# CMWX_LoRa_GPS_v14_Test.net
KiCad netlist of a schematic drawn in EAGLE
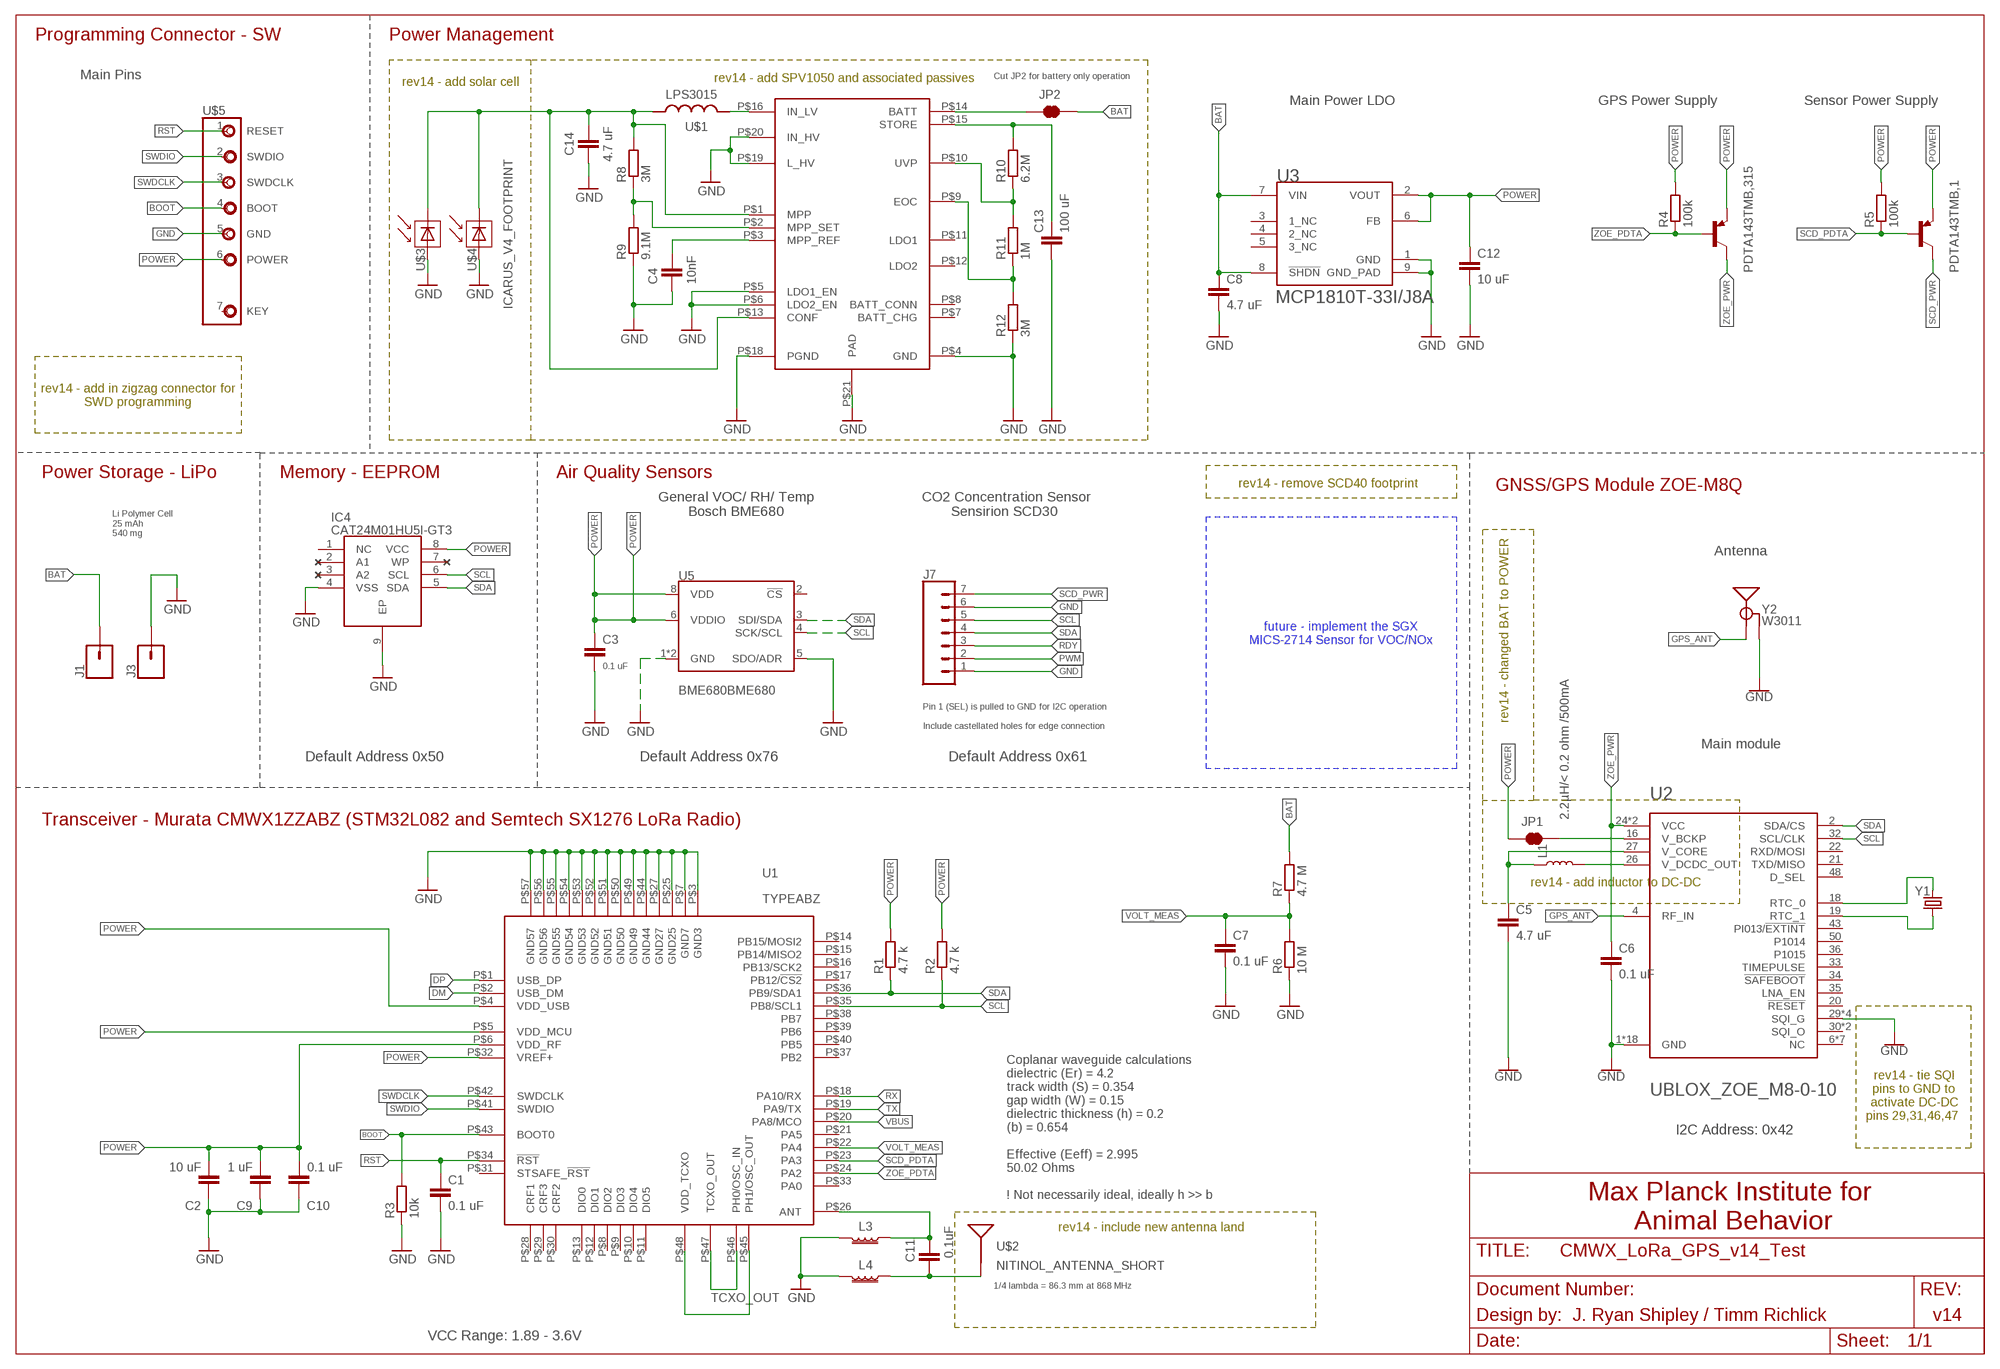
[diagram p0: schematic, sheet 1]

(export (version "E")
  (design (tool "Eeschema 10.0.6"))
  (components
    (comp (ref "C1")
      (value "0.1 uF")
      (footprint "eagle-import:C0201")
      (libsource (lib "eagle-import") (part "C-EUC0201"))
    )
    (comp (ref "C2")
      (value "10 uF")
      (footprint "eagle-import:C0201")
      (libsource (lib "eagle-import") (part "C-EUC0201"))
    )
    (comp (ref "C3")
      (value "0.1 uF")
      (footprint "eagle-import:C0201")
      (libsource (lib "eagle-import") (part "C-EUC0201"))
    )
    (comp (ref "C4")
      (value "10nF")
      (footprint "eagle-import:C0201")
      (libsource (lib "eagle-import") (part "C-EUC0201"))
    )
    (comp (ref "C5")
      (value "4.7 uF")
      (footprint "eagle-import:C0201")
      (libsource (lib "eagle-import") (part "C-EUC0201"))
    )
    (comp (ref "C6")
      (value "0.1 uF")
      (footprint "eagle-import:C0201")
      (libsource (lib "eagle-import") (part "C-EUC0201"))
    )
    (comp (ref "C7")
      (value "0.1 uF")
      (footprint "eagle-import:C0201")
      (libsource (lib "eagle-import") (part "C-EUC0201"))
    )
    (comp (ref "C8")
      (value "4.7 uF")
      (footprint "eagle-import:C0201")
      (libsource (lib "eagle-import") (part "C-EUC0201"))
    )
    (comp (ref "C9")
      (value "1 uF")
      (footprint "eagle-import:C0201")
      (libsource (lib "eagle-import") (part "C-EUC0201"))
    )
    (comp (ref "C10")
      (value "0.1 uF")
      (footprint "eagle-import:C0201")
      (libsource (lib "eagle-import") (part "C-EUC0201"))
    )
    (comp (ref "C11")
      (value "0.1uF")
      (footprint "eagle-import:0402-TIGHT")
      (libsource (lib "eagle-import") (part "0.1UF-0402T-16V-10%"))
    )
    (comp (ref "C12")
      (value "10 uF")
      (footprint "eagle-import:C0201")
      (libsource (lib "eagle-import") (part "C-EUC0201"))
    )
    (comp (ref "C13")
      (value "100 uF")
      (footprint "eagle-import:C0201")
      (libsource (lib "eagle-import") (part "C-EUC0201"))
    )
    (comp (ref "C14")
      (value "4.7 uF")
      (footprint "eagle-import:C0201")
      (libsource (lib "eagle-import") (part "C-EUC0201"))
    )
    (comp (ref "IC4")
      (value "CAT24M01HU5I-GT3")
      (footprint "eagle-import:SON50P300X200X55-9N")
      (fields
        (field (name "MOUSER_PART_NUMBER") "863-CAT24M01HU5I-GT3")
        (field (name "RS_PART_NUMBER") "7814831P")
      )
      (libsource (lib "eagle-import") (part "CAT24M01HU5I-GT3"))
    )
    (comp (ref "J1")
      (value "CONN_01PTH_NO_SILK_YES_STOP")
      (footprint "eagle-import:1X01_NO_SILK")
      (libsource (lib "eagle-import") (part "CONN_01PTH_NO_SILK_YES_STOP"))
    )
    (comp (ref "J3")
      (value "CONN_01PTH_NO_SILK_YES_STOP")
      (footprint "eagle-import:1X01_NO_SILK")
      (libsource (lib "eagle-import") (part "CONN_01PTH_NO_SILK_YES_STOP"))
    )
    (comp (ref "J7")
      (value "CONN_07NO_SILK")
      (footprint "eagle-import:1X07_NO_SILK")
      (libsource (lib "eagle-import") (part "CONN_07NO_SILK"))
    )
    (comp (ref "JP1")
      (value "JUMPER-SMT_2_NC_TRACE_NO-SILK")
      (footprint "eagle-import:SMT-JUMPER_2_NC_TRACE_NO-SILK")
      (libsource (lib "eagle-import") (part "JUMPER-SMT_2_NC_TRACE_NO-SILK"))
    )
    (comp (ref "JP2")
      (value "JUMPER-SMT_2_NC_TRACE_NO-SILK")
      (footprint "eagle-import:SMT-JUMPER_2_NC_TRACE_NO-SILK")
      (libsource (lib "eagle-import") (part "JUMPER-SMT_2_NC_TRACE_NO-SILK"))
    )
    (comp (ref "L1")
      (value "2.2µH/< 0.2 ohm /500mA")
      (footprint "eagle-import:0805")
      (libsource (lib "eagle-import") (part "INDUCTOR-0805-3.3UH"))
    )
    (comp (ref "L3")
      (value "FERRITE_BEAD-120_OHM_TIGHT")
      (footprint "eagle-import:0402-TIGHT")
      (libsource (lib "eagle-import") (part "FERRITE_BEAD-120_OHM_TIGHT"))
    )
    (comp (ref "L4")
      (value "FERRITE_BEAD-120_OHM_TIGHT")
      (footprint "eagle-import:0402-TIGHT")
      (libsource (lib "eagle-import") (part "FERRITE_BEAD-120_OHM_TIGHT"))
    )
    (comp (ref "PDTA143TMB,1")
      (value "TINYPICO-PNPAMB")
      (footprint "eagle-import:SOT883(B)")
      (libsource (lib "eagle-import") (part "TINYPICO-PNPMBA"))
    )
    (comp (ref "PDTA143TMB,315")
      (value "TINYPICO-PNPAMB")
      (footprint "eagle-import:SOT883(B)")
      (libsource (lib "eagle-import") (part "TINYPICO-PNPMBA"))
    )
    (comp (ref "R1")
      (value "4.7 k")
      (footprint "eagle-import:R0201")
      (libsource (lib "eagle-import") (part "R-EU_R0201"))
    )
    (comp (ref "R2")
      (value "4.7 k")
      (footprint "eagle-import:R0201")
      (libsource (lib "eagle-import") (part "R-EU_R0201"))
    )
    (comp (ref "R3")
      (value "10k")
      (footprint "eagle-import:R0201")
      (libsource (lib "eagle-import") (part "R-EU_R0201"))
    )
    (comp (ref "R4")
      (value "100k")
      (footprint "eagle-import:R0201")
      (libsource (lib "eagle-import") (part "R-EU_R0201"))
    )
    (comp (ref "R5")
      (value "100k")
      (footprint "eagle-import:R0201")
      (libsource (lib "eagle-import") (part "R-EU_R0201"))
    )
    (comp (ref "R6")
      (value "10 M")
      (footprint "eagle-import:R0201")
      (libsource (lib "eagle-import") (part "R-EU_R0201"))
    )
    (comp (ref "R7")
      (value "4.7 M")
      (footprint "eagle-import:R0201")
      (libsource (lib "eagle-import") (part "R-EU_R0201"))
    )
    (comp (ref "R8")
      (value "3M")
      (footprint "eagle-import:R0201")
      (libsource (lib "eagle-import") (part "R-EU_R0201"))
    )
    (comp (ref "R9")
      (value "9.1M")
      (footprint "eagle-import:R0201")
      (libsource (lib "eagle-import") (part "R-EU_R0201"))
    )
    (comp (ref "R10")
      (value "6.2M")
      (footprint "eagle-import:R0201")
      (libsource (lib "eagle-import") (part "R-EU_R0201"))
    )
    (comp (ref "R11")
      (value "1M")
      (footprint "eagle-import:R0201")
      (libsource (lib "eagle-import") (part "R-EU_R0201"))
    )
    (comp (ref "R12")
      (value "3M")
      (footprint "eagle-import:R0201")
      (libsource (lib "eagle-import") (part "R-EU_R0201"))
    )
    (comp (ref "U$1")
      (value "LPS3015")
      (footprint "eagle-import:LPS_3015")
      (libsource (lib "eagle-import") (part "LPS3015"))
    )
    (comp (ref "U$2")
      (value "NITINOL_ANTENNA_SHORT")
      (footprint "eagle-import:ICARUS_NITINOL_ANTENNA_SHORT")
      (libsource (lib "eagle-import") (part "NITINOL_ANTENNA_SHORT"))
    )
    (comp (ref "U$3")
      (value "ICARUS_V4_FOOTPRINT")
      (footprint "eagle-import:ICARUS_FULL_FOOTPRINT")
      (libsource (lib "eagle-import") (part "ICARUS_V4_FOOTPRINT"))
    )
    (comp (ref "U$4")
      (value "ICARUS_V4_FOOTPRINT")
      (footprint "eagle-import:ICARUS_FULL_FOOTPRINT")
      (libsource (lib "eagle-import") (part "ICARUS_V4_FOOTPRINT"))
    )
    (comp (ref "U$5")
      (value "ALBERT_ZIGZAG-ISP")
      (footprint "eagle-import:ALBERT_ZIGZAG-ISP")
      (libsource (lib "eagle-import") (part "ALBERT_ZIGZAG-ISP"))
    )
    (comp (ref "U1")
      (value "TYPEABZ")
      (footprint "eagle-import:TYPEABZ")
      (libsource (lib "eagle-import") (part "TYPEABZ"))
    )
    (comp (ref "U2")
      (value "UBLOX_ZOE_M8-0-10")
      (footprint "eagle-import:UBLOX_ZOE_M8-0-10")
      (libsource (lib "eagle-import") (part "UBLOX_ZOE_M8-0-10"))
    )
    (comp (ref "U3")
      (value "MICROCHIP_MCP1810T-33I-J8AMICROCHIP_MCP1810T-33I-J8A_0_0")
      (footprint "eagle-import:MICROCHIP_MCP1810T-33I-J8A_0")
      (fields
        (field (name "DIGIKEY_PART_NUMBER") "MCP1810T-33I/J8ACT-ND")
        (field (name "MF") "Microchip")
        (field (name "MOUSER_PART_NUMBER") "579-MCP1810T-33I/J8A")
      )
      (libsource (lib "eagle-import") (part "MICROCHIP_MCP1810T-33I-J8AMICROCHIP_MCP1810T-33I-J8A_0_0"))
    )
    (comp (ref "U4")
      (value "SPV1050")
      (footprint "eagle-import:SPV1050")
      (libsource (lib "eagle-import") (part "SPV1050"))
    )
    (comp (ref "U5")
      (value "BME680BME680")
      (footprint "eagle-import:LGA3.0X3.0")
      (libsource (lib "eagle-import") (part "BME680BME680"))
    )
    (comp (ref "Y1")
      (value "32.768kHz")
      (footprint "eagle-import:CRYSTAL-SMD-1.0X1.2MM")
      (libsource (lib "eagle-import") (part "CRYSTAL-32.768KHZ"))
    )
    (comp (ref "Y2")
      (value "W3011")
      (footprint "eagle-import:W3011")
      (libsource (lib "eagle-import") (part "GPS_CHIP_ANTENNAW3011"))
    )
  )
  (nets
    (net (code "1") (name "/TCXO_OUT") (class "Default")
      (node (ref "U1") (pin "P$46") (pinfunction "PH0/OSC_IN_P$46") (pintype "bidirectional"))
      (node (ref "U1") (pin "P$47") (pinfunction "TCXO_OUT_P$47") (pintype "bidirectional"))
    )
    (net (code "2") (name "BAT") (class "Default")
      (node (ref "C8") (pin "1") (pinfunction "1_1") (pintype "passive"))
      (node (ref "J1") (pin "1") (pinfunction "1_1") (pintype "passive"))
      (node (ref "JP2") (pin "2") (pinfunction "2_2") (pintype "passive"))
      (node (ref "R7") (pin "2") (pinfunction "2_2") (pintype "passive"))
      (node (ref "U3") (pin "7") (pinfunction "VIN_7") (pintype "bidirectional"))
      (node (ref "U3") (pin "8") (pinfunction "~{SHDN}_8") (pintype "bidirectional"))
    )
    (net (code "3") (name "BOOT") (class "Default")
      (node (ref "R3") (pin "2") (pinfunction "2_2") (pintype "passive"))
      (node (ref "U$5") (pin "4") (pinfunction "BOOT_4") (pintype "passive"))
      (node (ref "U1") (pin "P$43") (pinfunction "BOOT0_P$43") (pintype "bidirectional"))
    )
    (net (code "4") (name "DM") (class "Default")
      (node (ref "U1") (pin "P$2") (pinfunction "USB_DM_P$2") (pintype "bidirectional"))
    )
    (net (code "5") (name "DP") (class "Default")
      (node (ref "U1") (pin "P$1") (pinfunction "USB_DP_P$1") (pintype "bidirectional"))
    )
    (net (code "6") (name "GND") (class "Default")
      (node (ref "C1") (pin "2") (pinfunction "2_2") (pintype "passive"))
      (node (ref "C10") (pin "1") (pinfunction "1_1") (pintype "passive"))
      (node (ref "C12") (pin "2") (pinfunction "2_2") (pintype "passive"))
      (node (ref "C13") (pin "2") (pinfunction "2_2") (pintype "passive"))
      (node (ref "C14") (pin "2") (pinfunction "2_2") (pintype "passive"))
      (node (ref "C2") (pin "1") (pinfunction "1_1") (pintype "passive"))
      (node (ref "C3") (pin "2") (pinfunction "2_2") (pintype "passive"))
      (node (ref "C4") (pin "2") (pinfunction "2_2") (pintype "passive"))
      (node (ref "C5") (pin "2") (pinfunction "2_2") (pintype "passive"))
      (node (ref "C6") (pin "2") (pinfunction "2_2") (pintype "passive"))
      (node (ref "C7") (pin "2") (pinfunction "2_2") (pintype "passive"))
      (node (ref "C8") (pin "2") (pinfunction "2_2") (pintype "passive"))
      (node (ref "C9") (pin "1") (pinfunction "1_1") (pintype "passive"))
      (node (ref "IC4") (pin "4") (pinfunction "VSS_4") (pintype "power_in"))
      (node (ref "IC4") (pin "9") (pinfunction "EP_9") (pintype "bidirectional"))
      (node (ref "J3") (pin "1") (pinfunction "1_1") (pintype "passive"))
      (node (ref "J7") (pin "1") (pinfunction "1_1") (pintype "passive"))
      (node (ref "J7") (pin "6") (pinfunction "6_6") (pintype "passive"))
      (node (ref "L3") (pin "2") (pinfunction "2_2") (pintype "passive"))
      (node (ref "L4") (pin "2") (pinfunction "2_2") (pintype "passive"))
      (node (ref "R12") (pin "1") (pinfunction "1_1") (pintype "passive"))
      (node (ref "R3") (pin "1") (pinfunction "1_1") (pintype "passive"))
      (node (ref "R6") (pin "1") (pinfunction "1_1") (pintype "passive"))
      (node (ref "R9") (pin "1") (pinfunction "1_1") (pintype "passive"))
      (node (ref "U$3") (pin "P$3") (pinfunction "MINUS_P$3") (pintype "passive"))
      (node (ref "U$4") (pin "P$3") (pinfunction "MINUS_P$3") (pintype "passive"))
      (node (ref "U$5") (pin "5") (pinfunction "GND_5") (pintype "passive"))
      (node (ref "U1") (pin "P$25") (pinfunction "GND25_P$25") (pintype "power_in"))
      (node (ref "U1") (pin "P$27") (pinfunction "GND27_P$27") (pintype "power_in"))
      (node (ref "U1") (pin "P$3") (pinfunction "GND3_P$3") (pintype "power_in"))
      (node (ref "U1") (pin "P$44") (pinfunction "GND44_P$44") (pintype "power_in"))
      (node (ref "U1") (pin "P$49") (pinfunction "GND49_P$49") (pintype "power_in"))
      (node (ref "U1") (pin "P$50") (pinfunction "GND50_P$50") (pintype "power_in"))
      (node (ref "U1") (pin "P$51") (pinfunction "GND51_P$51") (pintype "power_in"))
      (node (ref "U1") (pin "P$52") (pinfunction "GND52_P$52") (pintype "power_in"))
      (node (ref "U1") (pin "P$53") (pinfunction "GND53_P$53") (pintype "power_in"))
      (node (ref "U1") (pin "P$54") (pinfunction "GND54_P$54") (pintype "power_in"))
      (node (ref "U1") (pin "P$55") (pinfunction "GND55_P$55") (pintype "power_in"))
      (node (ref "U1") (pin "P$56") (pinfunction "GND56_P$56") (pintype "power_in"))
      (node (ref "U1") (pin "P$57") (pinfunction "GND57_P$57") (pintype "power_in"))
      (node (ref "U1") (pin "P$7") (pinfunction "GND7_P$7") (pintype "power_in"))
      (node (ref "U2") (pin "1") (pinfunction "GND_1") (pintype "power_in"))
      (node (ref "U2") (pin "10") (pinfunction "GND_10") (pintype "power_in"))
      (node (ref "U2") (pin "11") (pinfunction "GND_11") (pintype "power_in"))
      (node (ref "U2") (pin "12") (pinfunction "GND_12") (pintype "power_in"))
      (node (ref "U2") (pin "17") (pinfunction "GND_17") (pintype "power_in"))
      (node (ref "U2") (pin "23") (pinfunction "GND_23") (pintype "power_in"))
      (node (ref "U2") (pin "29") (pinfunction "SQI_G_29") (pintype "bidirectional"))
      (node (ref "U2") (pin "3") (pinfunction "GND_3") (pintype "power_in"))
      (node (ref "U2") (pin "31") (pinfunction "SQI_G_31") (pintype "bidirectional"))
      (node (ref "U2") (pin "37") (pinfunction "GND_37") (pintype "power_in"))
      (node (ref "U2") (pin "38") (pinfunction "GND_38") (pintype "power_in"))
      (node (ref "U2") (pin "39") (pinfunction "GND_39") (pintype "power_in"))
      (node (ref "U2") (pin "40") (pinfunction "GND_40") (pintype "power_in"))
      (node (ref "U2") (pin "41") (pinfunction "GND_41") (pintype "power_in"))
      (node (ref "U2") (pin "44") (pinfunction "GND_44") (pintype "power_in"))
      (node (ref "U2") (pin "46") (pinfunction "SQI_G_46") (pintype "bidirectional"))
      (node (ref "U2") (pin "47") (pinfunction "SQI_G_47") (pintype "bidirectional"))
      (node (ref "U2") (pin "49") (pinfunction "GND_49") (pintype "power_in"))
      (node (ref "U2") (pin "5") (pinfunction "GND_5") (pintype "power_in"))
      (node (ref "U2") (pin "7") (pinfunction "GND_7") (pintype "power_in"))
      (node (ref "U2") (pin "8") (pinfunction "GND_8") (pintype "power_in"))
      (node (ref "U2") (pin "9") (pinfunction "GND_9") (pintype "power_in"))
      (node (ref "U3") (pin "1") (pinfunction "GND_1") (pintype "bidirectional"))
      (node (ref "U3") (pin "9") (pinfunction "GND_PAD_9") (pintype "bidirectional"))
      (node (ref "U4") (pin "P$18") (pinfunction "PGND_P$18") (pintype "power_in"))
      (node (ref "U4") (pin "P$19") (pinfunction "L_HV_P$19") (pintype "power_in"))
      (node (ref "U4") (pin "P$20") (pinfunction "IN_HV_P$20") (pintype "power_in"))
      (node (ref "U4") (pin "P$21") (pinfunction "PAD_P$21") (pintype "power_in"))
      (node (ref "U4") (pin "P$4") (pinfunction "GND_P$4") (pintype "power_in"))
      (node (ref "U4") (pin "P$5") (pinfunction "LDO1_EN_P$5") (pintype "input"))
      (node (ref "U4") (pin "P$6") (pinfunction "LDO2_EN_P$6") (pintype "input"))
      (node (ref "U5") (pin "1") (pinfunction "GND_1") (pintype "bidirectional"))
      (node (ref "U5") (pin "5") (pinfunction "SDO/ADR_5") (pintype "bidirectional"))
      (node (ref "U5") (pin "7") (pinfunction "GND_7") (pintype "bidirectional"))
      (node (ref "Y2") (pin "2") (pinfunction "GND_2") (pintype "bidirectional"))
      (node (ref "Y2") (pin "3") (pinfunction "GND_3") (pintype "bidirectional"))
    )
    (net (code "7") (name "GPS_ANT") (class "Default")
      (node (ref "U2") (pin "4") (pinfunction "RF_IN_4") (pintype "bidirectional"))
      (node (ref "Y2") (pin "1") (pinfunction "SIGNAL_1") (pintype "bidirectional"))
    )
    (net (code "8") (name "Net-(C11-Pad1)") (class "Default")
      (node (ref "C11") (pin "1") (pinfunction "1_1") (pintype "passive"))
      (node (ref "L4") (pin "1") (pinfunction "1_1") (pintype "passive"))
      (node (ref "U$2") (pin "1") (pinfunction "SIGNAL_1") (pintype "bidirectional"))
      (node (ref "U$2") (pin "2") (pinfunction "SIGNAL_2") (pintype "bidirectional"))
      (node (ref "U$2") (pin "3") (pinfunction "SIGNAL_3") (pintype "bidirectional"))
    )
    (net (code "9") (name "Net-(U$1-1)") (class "Default")
      (node (ref "C14") (pin "1") (pinfunction "1_1") (pintype "passive"))
      (node (ref "R8") (pin "2") (pinfunction "2_2") (pintype "passive"))
      (node (ref "U$1") (pin "P$1") (pinfunction "1_P$1") (pintype "passive"))
      (node (ref "U$3") (pin "P$1") (pinfunction "PLUS_P$1") (pintype "passive"))
      (node (ref "U$4") (pin "P$1") (pinfunction "PLUS_P$1") (pintype "passive"))
      (node (ref "U4") (pin "P$1") (pinfunction "MPP_P$1") (pintype "input"))
      (node (ref "U4") (pin "P$13") (pinfunction "CONF_P$13") (pintype "input"))
    )
    (net (code "10") (name "Net-(U$1-2)") (class "Default")
      (node (ref "U$1") (pin "P$2") (pinfunction "2_P$2") (pintype "passive"))
      (node (ref "U4") (pin "P$16") (pinfunction "IN_LV_P$16") (pintype "power_in"))
    )
    (net (code "11") (name "Net-(U1-ANT)") (class "Default")
      (node (ref "C11") (pin "2") (pinfunction "2_2") (pintype "passive"))
      (node (ref "L3") (pin "1") (pinfunction "1_1") (pintype "passive"))
      (node (ref "U1") (pin "P$26") (pinfunction "ANT_P$26") (pintype "bidirectional"))
    )
    (net (code "12") (name "Net-(U1-PH1{slash}OSC_OUT)") (class "Default")
      (node (ref "U1") (pin "P$45") (pinfunction "PH1/OSC_OUT_P$45") (pintype "bidirectional"))
      (node (ref "U1") (pin "P$48") (pinfunction "VDD_TCXO_P$48") (pintype "power_in"))
    )
    (net (code "13") (name "Net-(U2-RTC_0)") (class "Default")
      (node (ref "U2") (pin "18") (pinfunction "RTC_0_18") (pintype "bidirectional"))
      (node (ref "Y1") (pin "P$2") (pinfunction "2_P$2") (pintype "passive"))
    )
    (net (code "14") (name "Net-(U2-RTC_1)") (class "Default")
      (node (ref "U2") (pin "19") (pinfunction "RTC_1_19") (pintype "bidirectional"))
      (node (ref "Y1") (pin "P$1") (pinfunction "1_P$1") (pintype "passive"))
    )
    (net (code "15") (name "Net-(U2-V_BCKP)") (class "Default")
      (node (ref "JP1") (pin "2") (pinfunction "2_2") (pintype "passive"))
      (node (ref "U2") (pin "16") (pinfunction "V_BCKP_16") (pintype "power_in"))
    )
    (net (code "16") (name "Net-(U2-V_CORE)") (class "Default")
      (node (ref "C5") (pin "1") (pinfunction "1_1") (pintype "passive"))
      (node (ref "L1") (pin "1") (pinfunction "1_1") (pintype "passive"))
      (node (ref "U2") (pin "27") (pinfunction "V_CORE_27") (pintype "power_in"))
    )
    (net (code "17") (name "Net-(U2-V_DCDC_OUT)") (class "Default")
      (node (ref "L1") (pin "2") (pinfunction "2_2") (pintype "passive"))
      (node (ref "U2") (pin "26") (pinfunction "V_DCDC_OUT_26") (pintype "power_in"))
    )
    (net (code "18") (name "Net-(U4-BATT)") (class "Default")
      (node (ref "JP2") (pin "1") (pinfunction "1_1") (pintype "passive"))
      (node (ref "U4") (pin "P$14") (pinfunction "BATT_P$14") (pintype "bidirectional"))
    )
    (net (code "19") (name "Net-(U4-EOC)") (class "Default")
      (node (ref "R11") (pin "1") (pinfunction "1_1") (pintype "passive"))
      (node (ref "R12") (pin "2") (pinfunction "2_2") (pintype "passive"))
      (node (ref "U4") (pin "P$9") (pinfunction "EOC_P$9") (pintype "input"))
    )
    (net (code "20") (name "Net-(U4-MPP_REF)") (class "Default")
      (node (ref "C4") (pin "1") (pinfunction "1_1") (pintype "passive"))
      (node (ref "U4") (pin "P$3") (pinfunction "MPP_REF_P$3") (pintype "input"))
    )
    (net (code "21") (name "Net-(U4-MPP_SET)") (class "Default")
      (node (ref "R8") (pin "1") (pinfunction "1_1") (pintype "passive"))
      (node (ref "R9") (pin "2") (pinfunction "2_2") (pintype "passive"))
      (node (ref "U4") (pin "P$2") (pinfunction "MPP_SET_P$2") (pintype "input"))
    )
    (net (code "22") (name "Net-(U4-STORE)") (class "Default")
      (node (ref "C13") (pin "1") (pinfunction "1_1") (pintype "passive"))
      (node (ref "R10") (pin "2") (pinfunction "2_2") (pintype "passive"))
      (node (ref "U4") (pin "P$15") (pinfunction "STORE_P$15") (pintype "bidirectional"))
    )
    (net (code "23") (name "Net-(U4-UVP)") (class "Default")
      (node (ref "R10") (pin "1") (pinfunction "1_1") (pintype "passive"))
      (node (ref "R11") (pin "2") (pinfunction "2_2") (pintype "passive"))
      (node (ref "U4") (pin "P$10") (pinfunction "UVP_P$10") (pintype "input"))
    )
    (net (code "24") (name "POWER") (class "Default")
      (node (ref "C10") (pin "2") (pinfunction "2_2") (pintype "passive"))
      (node (ref "C12") (pin "1") (pinfunction "1_1") (pintype "passive"))
      (node (ref "C2") (pin "2") (pinfunction "2_2") (pintype "passive"))
      (node (ref "C3") (pin "1") (pinfunction "1_1") (pintype "passive"))
      (node (ref "C9") (pin "2") (pinfunction "2_2") (pintype "passive"))
      (node (ref "IC4") (pin "8") (pinfunction "VCC_8") (pintype "power_in"))
      (node (ref "JP1") (pin "1") (pinfunction "1_1") (pintype "passive"))
      (node (ref "PDTA143TMB,1") (pin "2") (pinfunction "E_2") (pintype "passive"))
      (node (ref "PDTA143TMB,315") (pin "2") (pinfunction "E_2") (pintype "passive"))
      (node (ref "R1") (pin "2") (pinfunction "2_2") (pintype "passive"))
      (node (ref "R2") (pin "2") (pinfunction "2_2") (pintype "passive"))
      (node (ref "R4") (pin "2") (pinfunction "2_2") (pintype "passive"))
      (node (ref "R5") (pin "2") (pinfunction "2_2") (pintype "passive"))
      (node (ref "U$5") (pin "6") (pinfunction "POWER_6") (pintype "passive"))
      (node (ref "U1") (pin "P$32") (pinfunction "VREF+_P$32") (pintype "power_in"))
      (node (ref "U1") (pin "P$4") (pinfunction "VDD_USB_P$4") (pintype "power_in"))
      (node (ref "U1") (pin "P$5") (pinfunction "VDD_MCU_P$5") (pintype "power_in"))
      (node (ref "U1") (pin "P$6") (pinfunction "VDD_RF_P$6") (pintype "power_in"))
      (node (ref "U3") (pin "2") (pinfunction "VOUT_2") (pintype "bidirectional"))
      (node (ref "U3") (pin "6") (pinfunction "FB_6") (pintype "bidirectional"))
      (node (ref "U5") (pin "6") (pinfunction "VDDIO_6") (pintype "bidirectional"))
      (node (ref "U5") (pin "8") (pinfunction "VDD_8") (pintype "bidirectional"))
    )
    (net (code "25") (name "PWM") (class "Default")
      (node (ref "J7") (pin "2") (pinfunction "2_2") (pintype "passive"))
    )
    (net (code "26") (name "RDY") (class "Default")
      (node (ref "J7") (pin "3") (pinfunction "3_3") (pintype "passive"))
    )
    (net (code "27") (name "RST") (class "Default")
      (node (ref "C1") (pin "1") (pinfunction "1_1") (pintype "passive"))
      (node (ref "U$5") (pin "1") (pinfunction "RESET_1") (pintype "passive"))
      (node (ref "U1") (pin "P$34") (pinfunction "~{RST}_P$34") (pintype "bidirectional"))
    )
    (net (code "28") (name "RX") (class "Default")
      (node (ref "U1") (pin "P$18") (pinfunction "PA10/RX_P$18") (pintype "bidirectional"))
    )
    (net (code "29") (name "SCD_PDTA") (class "Default")
      (node (ref "PDTA143TMB,1") (pin "1") (pinfunction "B_1") (pintype "passive"))
      (node (ref "R5") (pin "1") (pinfunction "1_1") (pintype "passive"))
      (node (ref "U1") (pin "P$23") (pinfunction "PA3_P$23") (pintype "bidirectional"))
    )
    (net (code "30") (name "SCD_PWR") (class "Default")
      (node (ref "J7") (pin "7") (pinfunction "7_7") (pintype "passive"))
      (node (ref "PDTA143TMB,1") (pin "3") (pinfunction "C_3") (pintype "passive"))
    )
    (net (code "31") (name "SCL") (class "Default")
      (node (ref "IC4") (pin "6") (pinfunction "SCL_6") (pintype "bidirectional"))
      (node (ref "J7") (pin "5") (pinfunction "5_5") (pintype "passive"))
      (node (ref "R2") (pin "1") (pinfunction "1_1") (pintype "passive"))
      (node (ref "U1") (pin "P$35") (pinfunction "PB8/SCL1_P$35") (pintype "bidirectional"))
      (node (ref "U2") (pin "32") (pinfunction "SCL/CLK_32") (pintype "bidirectional"))
      (node (ref "U5") (pin "4") (pinfunction "SCK/SCL_4") (pintype "bidirectional"))
    )
    (net (code "32") (name "SDA") (class "Default")
      (node (ref "IC4") (pin "5") (pinfunction "SDA_5") (pintype "bidirectional"))
      (node (ref "J7") (pin "4") (pinfunction "4_4") (pintype "passive"))
      (node (ref "R1") (pin "1") (pinfunction "1_1") (pintype "passive"))
      (node (ref "U1") (pin "P$36") (pinfunction "PB9/SDA1_P$36") (pintype "bidirectional"))
      (node (ref "U2") (pin "2") (pinfunction "SDA/CS_2") (pintype "bidirectional"))
      (node (ref "U5") (pin "3") (pinfunction "SDI/SDA_3") (pintype "bidirectional"))
    )
    (net (code "33") (name "SWDCLK") (class "Default")
      (node (ref "U$5") (pin "3") (pinfunction "SWDCLK_3") (pintype "passive"))
      (node (ref "U1") (pin "P$42") (pinfunction "SWDCLK_P$42") (pintype "bidirectional"))
    )
    (net (code "34") (name "SWDIO") (class "Default")
      (node (ref "U$5") (pin "2") (pinfunction "SWDIO_2") (pintype "passive"))
      (node (ref "U1") (pin "P$41") (pinfunction "SWDIO_P$41") (pintype "bidirectional"))
    )
    (net (code "35") (name "TX") (class "Default")
      (node (ref "U1") (pin "P$19") (pinfunction "PA9/TX_P$19") (pintype "bidirectional"))
    )
    (net (code "36") (name "VBUS") (class "Default")
      (node (ref "U1") (pin "P$20") (pinfunction "PA8/MCO_P$20") (pintype "bidirectional"))
    )
    (net (code "37") (name "VOLT_MEAS") (class "Default")
      (node (ref "C7") (pin "1") (pinfunction "1_1") (pintype "passive"))
      (node (ref "R6") (pin "2") (pinfunction "2_2") (pintype "passive"))
      (node (ref "R7") (pin "1") (pinfunction "1_1") (pintype "passive"))
      (node (ref "U1") (pin "P$22") (pinfunction "PA4_P$22") (pintype "bidirectional"))
    )
    (net (code "38") (name "ZOE_PDTA") (class "Default")
      (node (ref "PDTA143TMB,315") (pin "1") (pinfunction "B_1") (pintype "passive"))
      (node (ref "R4") (pin "1") (pinfunction "1_1") (pintype "passive"))
      (node (ref "U1") (pin "P$24") (pinfunction "PA2_P$24") (pintype "bidirectional"))
    )
    (net (code "39") (name "ZOE_PWR") (class "Default")
      (node (ref "C6") (pin "1") (pinfunction "1_1") (pintype "passive"))
      (node (ref "PDTA143TMB,315") (pin "3") (pinfunction "C_3") (pintype "passive"))
      (node (ref "U2") (pin "24") (pinfunction "VCC_24") (pintype "power_in"))
      (node (ref "U2") (pin "25") (pinfunction "VCC_25") (pintype "power_in"))
    )
    (net (code "40") (name "unconnected-(IC4-A1-Pad2)") (class "Default")
      (node (ref "IC4") (pin "2") (pinfunction "A1_2") (pintype "bidirectional"))
    )
    (net (code "41") (name "unconnected-(IC4-A2-Pad3)") (class "Default")
      (node (ref "IC4") (pin "3") (pinfunction "A2_3") (pintype "bidirectional"))
    )
    (net (code "42") (name "unconnected-(IC4-NC-Pad1)") (class "Default")
      (node (ref "IC4") (pin "1") (pinfunction "NC_1") (pintype "no_connect"))
    )
    (net (code "43") (name "unconnected-(IC4-WP-Pad7)") (class "Default")
      (node (ref "IC4") (pin "7") (pinfunction "WP_7") (pintype "bidirectional"))
    )
    (net (code "44") (name "unconnected-(U$5-KEY-Pad7)") (class "Default")
      (node (ref "U$5") (pin "7") (pinfunction "KEY_7") (pintype "passive"))
    )
    (net (code "45") (name "unconnected-(U1-CRF1-PadP$28)") (class "Default")
      (node (ref "U1") (pin "P$28") (pinfunction "CRF1_P$28") (pintype "no_connect"))
    )
    (net (code "46") (name "unconnected-(U1-CRF2-PadP$30)") (class "Default")
      (node (ref "U1") (pin "P$30") (pinfunction "CRF2_P$30") (pintype "no_connect"))
    )
    (net (code "47") (name "unconnected-(U1-CRF3-PadP$29)") (class "Default")
      (node (ref "U1") (pin "P$29") (pinfunction "CRF3_P$29") (pintype "no_connect"))
    )
    (net (code "48") (name "unconnected-(U1-DIO0-PadP$13)") (class "Default")
      (node (ref "U1") (pin "P$13") (pinfunction "DIO0_P$13") (pintype "no_connect"))
    )
    (net (code "49") (name "unconnected-(U1-DIO1-PadP$12)") (class "Default")
      (node (ref "U1") (pin "P$12") (pinfunction "DIO1_P$12") (pintype "no_connect"))
    )
    (net (code "50") (name "unconnected-(U1-DIO2-PadP$8)") (class "Default")
      (node (ref "U1") (pin "P$8") (pinfunction "DIO2_P$8") (pintype "no_connect"))
    )
    (net (code "51") (name "unconnected-(U1-DIO3-PadP$9)") (class "Default")
      (node (ref "U1") (pin "P$9") (pinfunction "DIO3_P$9") (pintype "no_connect"))
    )
    (net (code "52") (name "unconnected-(U1-DIO4-PadP$10)") (class "Default")
      (node (ref "U1") (pin "P$10") (pinfunction "DIO4_P$10") (pintype "bidirectional"))
    )
    (net (code "53") (name "unconnected-(U1-DIO5-PadP$11)") (class "Default")
      (node (ref "U1") (pin "P$11") (pinfunction "DIO5_P$11") (pintype "bidirectional"))
    )
    (net (code "54") (name "unconnected-(U1-PA0-PadP$33)") (class "Default")
      (node (ref "U1") (pin "P$33") (pinfunction "PA0_P$33") (pintype "bidirectional"))
    )
    (net (code "55") (name "unconnected-(U1-PA5-PadP$21)") (class "Default")
      (node (ref "U1") (pin "P$21") (pinfunction "PA5_P$21") (pintype "bidirectional"))
    )
    (net (code "56") (name "unconnected-(U1-PB2-PadP$37)") (class "Default")
      (node (ref "U1") (pin "P$37") (pinfunction "PB2_P$37") (pintype "bidirectional"))
    )
    (net (code "57") (name "unconnected-(U1-PB5-PadP$40)") (class "Default")
      (node (ref "U1") (pin "P$40") (pinfunction "PB5_P$40") (pintype "bidirectional"))
    )
    (net (code "58") (name "unconnected-(U1-PB6-PadP$39)") (class "Default")
      (node (ref "U1") (pin "P$39") (pinfunction "PB6_P$39") (pintype "bidirectional"))
    )
    (net (code "59") (name "unconnected-(U1-PB7-PadP$38)") (class "Default")
      (node (ref "U1") (pin "P$38") (pinfunction "PB7_P$38") (pintype "bidirectional"))
    )
    (net (code "60") (name "unconnected-(U1-PB12{slash}~{CS2}-PadP$17)") (class "Default")
      (node (ref "U1") (pin "P$17") (pinfunction "PB12/~{CS2}_P$17") (pintype "bidirectional"))
    )
    (net (code "61") (name "unconnected-(U1-PB13{slash}SCK2-PadP$16)") (class "Default")
      (node (ref "U1") (pin "P$16") (pinfunction "PB13/SCK2_P$16") (pintype "bidirectional"))
    )
    (net (code "62") (name "unconnected-(U1-PB14{slash}MISO2-PadP$15)") (class "Default")
      (node (ref "U1") (pin "P$15") (pinfunction "PB14/MISO2_P$15") (pintype "bidirectional"))
    )
    (net (code "63") (name "unconnected-(U1-PB15{slash}MOSI2-PadP$14)") (class "Default")
      (node (ref "U1") (pin "P$14") (pinfunction "PB15/MOSI2_P$14") (pintype "bidirectional"))
    )
    (net (code "64") (name "unconnected-(U1-STSAFE_~{RST}-PadP$31)") (class "Default")
      (node (ref "U1") (pin "P$31") (pinfunction "STSAFE_~{RST}_P$31") (pintype "bidirectional"))
    )
    (net (code "65") (name "unconnected-(U2-D_SEL-Pad48)") (class "Default")
      (node (ref "U2") (pin "48") (pinfunction "D_SEL_48") (pintype "bidirectional"))
    )
    (net (code "66") (name "unconnected-(U2-LNA_EN-Pad35)") (class "Default")
      (node (ref "U2") (pin "35") (pinfunction "LNA_EN_35") (pintype "bidirectional"))
    )
    (net (code "67") (name "unconnected-(U2-NC-Pad6)") (class "Default")
      (node (ref "U2") (pin "6") (pinfunction "NC_6") (pintype "no_connect"))
    )
    (net (code "68") (name "unconnected-(U2-NC-Pad13)") (class "Default")
      (node (ref "U2") (pin "13") (pinfunction "NC_13") (pintype "no_connect"))
    )
    (net (code "69") (name "unconnected-(U2-NC-Pad14)") (class "Default")
      (node (ref "U2") (pin "14") (pinfunction "NC_14") (pintype "no_connect"))
    )
    (net (code "70") (name "unconnected-(U2-NC-Pad15)") (class "Default")
      (node (ref "U2") (pin "15") (pinfunction "NC_15") (pintype "no_connect"))
    )
    (net (code "71") (name "unconnected-(U2-NC-Pad28)") (class "Default")
      (node (ref "U2") (pin "28") (pinfunction "NC_28") (pintype "no_connect"))
    )
    (net (code "72") (name "unconnected-(U2-NC-Pad42)") (class "Default")
      (node (ref "U2") (pin "42") (pinfunction "NC_42") (pintype "no_connect"))
    )
    (net (code "73") (name "unconnected-(U2-NC-Pad51)") (class "Default")
      (node (ref "U2") (pin "51") (pinfunction "NC_51") (pintype "no_connect"))
    )
    (net (code "74") (name "unconnected-(U2-P1014-Pad50)") (class "Default")
      (node (ref "U2") (pin "50") (pinfunction "P1014_50") (pintype "bidirectional"))
    )
    (net (code "75") (name "unconnected-(U2-P1015-Pad36)") (class "Default")
      (node (ref "U2") (pin "36") (pinfunction "P1015_36") (pintype "bidirectional"))
    )
    (net (code "76") (name "unconnected-(U2-PI013{slash}~{EXTINT}-Pad43)") (class "Default")
      (node (ref "U2") (pin "43") (pinfunction "PI013/~{EXTINT}_43") (pintype "bidirectional"))
    )
    (net (code "77") (name "unconnected-(U2-RXD{slash}MOSI-Pad22)") (class "Default")
      (node (ref "U2") (pin "22") (pinfunction "RXD/MOSI_22") (pintype "bidirectional"))
    )
    (net (code "78") (name "unconnected-(U2-SQI_O-Pad30)") (class "Default")
      (node (ref "U2") (pin "30") (pinfunction "SQI_O_30") (pintype "no_connect"))
    )
    (net (code "79") (name "unconnected-(U2-SQI_O-Pad45)") (class "Default")
      (node (ref "U2") (pin "45") (pinfunction "SQI_O_45") (pintype "no_connect"))
    )
    (net (code "80") (name "unconnected-(U2-TIMEPULSE-Pad33)") (class "Default")
      (node (ref "U2") (pin "33") (pinfunction "TIMEPULSE_33") (pintype "bidirectional"))
    )
    (net (code "81") (name "unconnected-(U2-TXD{slash}MISO-Pad21)") (class "Default")
      (node (ref "U2") (pin "21") (pinfunction "TXD/MISO_21") (pintype "bidirectional"))
    )
    (net (code "82") (name "unconnected-(U2-~{RESET}-Pad20)") (class "Default")
      (node (ref "U2") (pin "20") (pinfunction "~{RESET}_20") (pintype "bidirectional"))
    )
    (net (code "83") (name "unconnected-(U2-~{SAFEBOOT}-Pad34)") (class "Default")
      (node (ref "U2") (pin "34") (pinfunction "~{SAFEBOOT}_34") (pintype "bidirectional"))
    )
    (net (code "84") (name "unconnected-(U3-1_NC-Pad3)") (class "Default")
      (node (ref "U3") (pin "3") (pinfunction "1_NC_3") (pintype "bidirectional"))
    )
    (net (code "85") (name "unconnected-(U3-2_NC-Pad4)") (class "Default")
      (node (ref "U3") (pin "4") (pinfunction "2_NC_4") (pintype "bidirectional"))
    )
    (net (code "86") (name "unconnected-(U3-3_NC-Pad5)") (class "Default")
      (node (ref "U3") (pin "5") (pinfunction "3_NC_5") (pintype "bidirectional"))
    )
    (net (code "87") (name "unconnected-(U4-BATT_CHG-PadP$7)") (class "Default")
      (node (ref "U4") (pin "P$7") (pinfunction "BATT_CHG_P$7") (pintype "open_collector"))
    )
    (net (code "88") (name "unconnected-(U4-BATT_CONN-PadP$8)") (class "Default")
      (node (ref "U4") (pin "P$8") (pinfunction "BATT_CONN_P$8") (pintype "open_collector"))
    )
    (net (code "89") (name "unconnected-(U4-LDO1-PadP$11)") (class "Default")
      (node (ref "U4") (pin "P$11") (pinfunction "LDO1_P$11") (pintype "output"))
    )
    (net (code "90") (name "unconnected-(U4-LDO2-PadP$12)") (class "Default")
      (node (ref "U4") (pin "P$12") (pinfunction "LDO2_P$12") (pintype "output"))
    )
    (net (code "91") (name "unconnected-(U5-~{CS}-Pad2)") (class "Default")
      (node (ref "U5") (pin "2") (pinfunction "~{CS}_2") (pintype "bidirectional"))
    )
  )
)
